# Debug_adapter.net
KiCad netlist of a schematic drawn in EAGLE
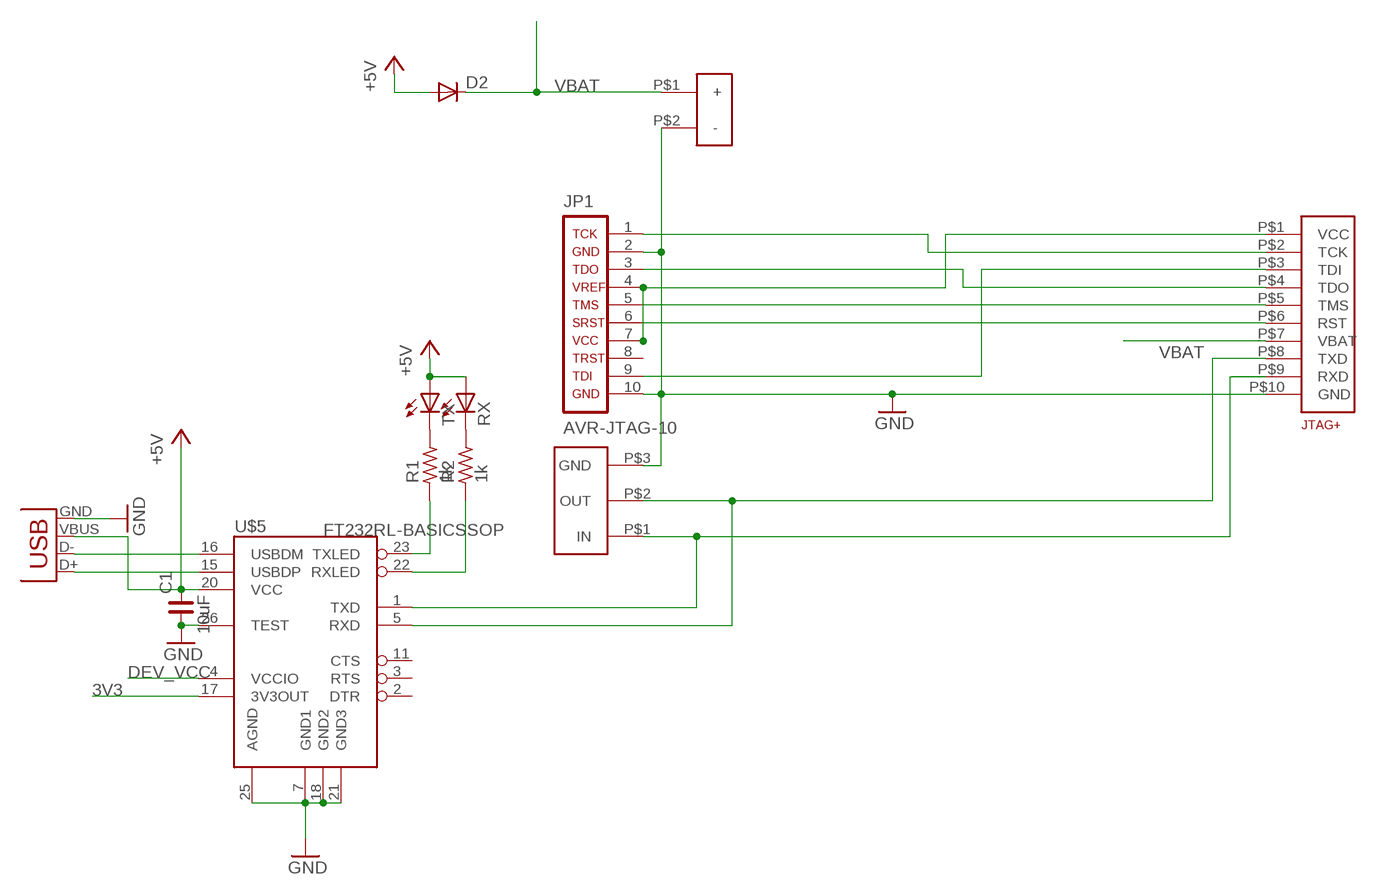
[diagram p0: schematic, sheet 1]

(export (version "E")
  (design (tool "Eeschema 10.0.6"))
  (components
    (comp (ref "C1")
      (value "10uF")
      (footprint "eagle-import:C0805")
      (libsource (lib "eagle-import") (part "C_0805"))
    )
    (comp (ref "D2")
      (value "DIODESOD")
      (footprint "eagle-import:SOD-323")
      (libsource (lib "eagle-import") (part "DIODESOD"))
    )
    (comp (ref "JP1")
      (value "AVR-JTAG-10")
      (footprint "eagle-import:AVR-JTAG-10")
      (libsource (lib "eagle-import") (part "AVR-JTAG-10"))
    )
    (comp (ref "R1")
      (value "1k")
      (footprint "eagle-import:R0805")
      (libsource (lib "eagle-import") (part "R_0805"))
    )
    (comp (ref "R2")
      (value "1k")
      (footprint "eagle-import:R0805")
      (libsource (lib "eagle-import") (part "R_0805"))
    )
    (comp (ref "RX")
      (value "LEDCHIPLED_0805")
      (footprint "eagle-import:CHIPLED_0805")
      (libsource (lib "eagle-import") (part "LEDCHIPLED_0805"))
    )
    (comp (ref "TX")
      (value "LEDCHIPLED_0805")
      (footprint "eagle-import:CHIPLED_0805")
      (libsource (lib "eagle-import") (part "LEDCHIPLED_0805"))
    )
    (comp (ref "U$1")
      (value "AVR32_JTAG+SERIAL")
      (footprint "eagle-import:MOLEX_CONNECTOR_10PINS")
      (libsource (lib "eagle-import") (part "AVR32_JTAG+SERIAL"))
    )
    (comp (ref "U$2")
      (value "POWER")
      (footprint "eagle-import:POWER")
      (libsource (lib "eagle-import") (part "POWER"))
    )
    (comp (ref "U$3")
      (value "SERIAL")
      (footprint "eagle-import:SERVO")
      (libsource (lib "eagle-import") (part "SERIAL"))
    )
    (comp (ref "U$5")
      (value "FT232RL-BASICSSOP")
      (footprint "eagle-import:SSOP28DB")
      (libsource (lib "eagle-import") (part "FT232RL-BASICSSOP"))
    )
    (comp (ref "X1")
      (value "USBSMD")
      (footprint "eagle-import:USB-MINIB")
      (libsource (lib "eagle-import") (part "USBSMD"))
    )
  )
  (nets
    (net (code "1") (name "+5V") (class "Default")
      (node (ref "C1") (pin "2") (pinfunction "2_2") (pintype "passive"))
      (node (ref "D2") (pin "2") (pinfunction "A_2") (pintype "passive"))
      (node (ref "RX") (pin "A") (pinfunction "A_A") (pintype "passive"))
      (node (ref "TX") (pin "A") (pinfunction "A_A") (pintype "passive"))
      (node (ref "U$5") (pin "20") (pinfunction "VCC_20") (pintype "power_in"))
      (node (ref "X1") (pin "VBUS") (pinfunction "VBUS_VBUS") (pintype "bidirectional"))
    )
    (net (code "2") (name "/3V3") (class "Default")
      (node (ref "U$5") (pin "17") (pinfunction "3V3OUT_17") (pintype "output"))
    )
    (net (code "3") (name "/DEV_VCC") (class "Default")
      (node (ref "U$5") (pin "4") (pinfunction "VCCIO_4") (pintype "power_in"))
    )
    (net (code "4") (name "/VBAT") (class "Default")
      (node (ref "D2") (pin "1") (pinfunction "C_1") (pintype "passive"))
      (node (ref "U$1") (pin "P$7") (pinfunction "VBAT_P$7") (pintype "bidirectional"))
      (node (ref "U$2") (pin "P$1") (pinfunction "+_P$1") (pintype "bidirectional"))
    )
    (net (code "5") (name "GND") (class "Default")
      (node (ref "C1") (pin "1") (pinfunction "1_1") (pintype "passive"))
      (node (ref "JP1") (pin "10") (pinfunction "10_10") (pintype "passive"))
      (node (ref "JP1") (pin "2") (pinfunction "2_2") (pintype "passive"))
      (node (ref "U$1") (pin "P$10") (pinfunction "GND_P$10") (pintype "bidirectional"))
      (node (ref "U$2") (pin "P$2") (pinfunction "-_P$2") (pintype "bidirectional"))
      (node (ref "U$3") (pin "P$3") (pinfunction "GND_P$3") (pintype "bidirectional"))
      (node (ref "U$5") (pin "18") (pinfunction "GND2_18") (pintype "power_in"))
      (node (ref "U$5") (pin "21") (pinfunction "GND3_21") (pintype "power_in"))
      (node (ref "U$5") (pin "25") (pinfunction "AGND_25") (pintype "power_in"))
      (node (ref "U$5") (pin "26") (pinfunction "TEST_26") (pintype "input"))
      (node (ref "U$5") (pin "7") (pinfunction "GND1_7") (pintype "power_in"))
      (node (ref "X1") (pin "GND") (pinfunction "GND_GND") (pintype "bidirectional"))
    )
    (net (code "6") (name "Net-(R1-Pad2)") (class "Default")
      (node (ref "R1") (pin "2") (pinfunction "2_2") (pintype "passive"))
      (node (ref "TX") (pin "C") (pinfunction "C_C") (pintype "passive"))
    )
    (net (code "7") (name "Net-(R2-Pad2)") (class "Default")
      (node (ref "R2") (pin "2") (pinfunction "2_2") (pintype "passive"))
      (node (ref "RX") (pin "C") (pinfunction "C_C") (pintype "passive"))
    )
    (net (code "8") (name "Net-(U$1-RST)") (class "Default")
      (node (ref "JP1") (pin "6") (pinfunction "6_6") (pintype "passive"))
      (node (ref "U$1") (pin "P$6") (pinfunction "RST_P$6") (pintype "bidirectional"))
    )
    (net (code "9") (name "Net-(U$1-RXD)") (class "Default")
      (node (ref "U$1") (pin "P$9") (pinfunction "RXD_P$9") (pintype "bidirectional"))
      (node (ref "U$3") (pin "P$1") (pinfunction "IN_P$1") (pintype "bidirectional"))
      (node (ref "U$5") (pin "1") (pinfunction "TXD_1") (pintype "output"))
    )
    (net (code "10") (name "Net-(U$1-TCK)") (class "Default")
      (node (ref "JP1") (pin "1") (pinfunction "1_1") (pintype "passive"))
      (node (ref "U$1") (pin "P$2") (pinfunction "TCK_P$2") (pintype "bidirectional"))
    )
    (net (code "11") (name "Net-(U$1-TDI)") (class "Default")
      (node (ref "JP1") (pin "9") (pinfunction "9_9") (pintype "passive"))
      (node (ref "U$1") (pin "P$3") (pinfunction "TDI_P$3") (pintype "bidirectional"))
    )
    (net (code "12") (name "Net-(U$1-TDO)") (class "Default")
      (node (ref "JP1") (pin "3") (pinfunction "3_3") (pintype "passive"))
      (node (ref "U$1") (pin "P$4") (pinfunction "TDO_P$4") (pintype "bidirectional"))
    )
    (net (code "13") (name "Net-(U$1-TMS)") (class "Default")
      (node (ref "JP1") (pin "5") (pinfunction "5_5") (pintype "passive"))
      (node (ref "U$1") (pin "P$5") (pinfunction "TMS_P$5") (pintype "bidirectional"))
    )
    (net (code "14") (name "Net-(U$1-TXD)") (class "Default")
      (node (ref "U$1") (pin "P$8") (pinfunction "TXD_P$8") (pintype "bidirectional"))
      (node (ref "U$3") (pin "P$2") (pinfunction "OUT_P$2") (pintype "bidirectional"))
      (node (ref "U$5") (pin "5") (pinfunction "RXD_5") (pintype "input"))
    )
    (net (code "15") (name "Net-(U$1-VCC)") (class "Default")
      (node (ref "JP1") (pin "4") (pinfunction "4_4") (pintype "passive"))
      (node (ref "JP1") (pin "7") (pinfunction "7_7") (pintype "passive"))
      (node (ref "U$1") (pin "P$1") (pinfunction "VCC_P$1") (pintype "bidirectional"))
    )
    (net (code "16") (name "Net-(U$5-RXLED)") (class "Default")
      (node (ref "R2") (pin "1") (pinfunction "1_1") (pintype "passive"))
      (node (ref "U$5") (pin "22") (pinfunction "RXLED_22") (pintype "bidirectional"))
    )
    (net (code "17") (name "Net-(U$5-TXLED)") (class "Default")
      (node (ref "R1") (pin "1") (pinfunction "1_1") (pintype "passive"))
      (node (ref "U$5") (pin "23") (pinfunction "TXLED_23") (pintype "bidirectional"))
    )
    (net (code "18") (name "Net-(U$5-USBDM)") (class "Default")
      (node (ref "U$5") (pin "16") (pinfunction "USBDM_16") (pintype "bidirectional"))
      (node (ref "X1") (pin "D-") (pinfunction "D-_D-") (pintype "bidirectional"))
    )
    (net (code "19") (name "Net-(U$5-USBDP)") (class "Default")
      (node (ref "U$5") (pin "15") (pinfunction "USBDP_15") (pintype "bidirectional"))
      (node (ref "X1") (pin "D+") (pinfunction "D+_D+") (pintype "bidirectional"))
    )
    (net (code "20") (name "unconnected-(JP1-Pad8)") (class "Default")
      (node (ref "JP1") (pin "8") (pinfunction "8_8") (pintype "passive"))
    )
    (net (code "21") (name "unconnected-(U$5-CTS-Pad11)") (class "Default")
      (node (ref "U$5") (pin "11") (pinfunction "CTS_11") (pintype "bidirectional"))
    )
    (net (code "22") (name "unconnected-(U$5-DTR-Pad2)") (class "Default")
      (node (ref "U$5") (pin "2") (pinfunction "DTR_2") (pintype "bidirectional"))
    )
    (net (code "23") (name "unconnected-(U$5-RTS-Pad3)") (class "Default")
      (node (ref "U$5") (pin "3") (pinfunction "RTS_3") (pintype "bidirectional"))
    )
  )
)
